# EEPROM_Temp.net
KiCad netlist of a schematic drawn in Altium Designer
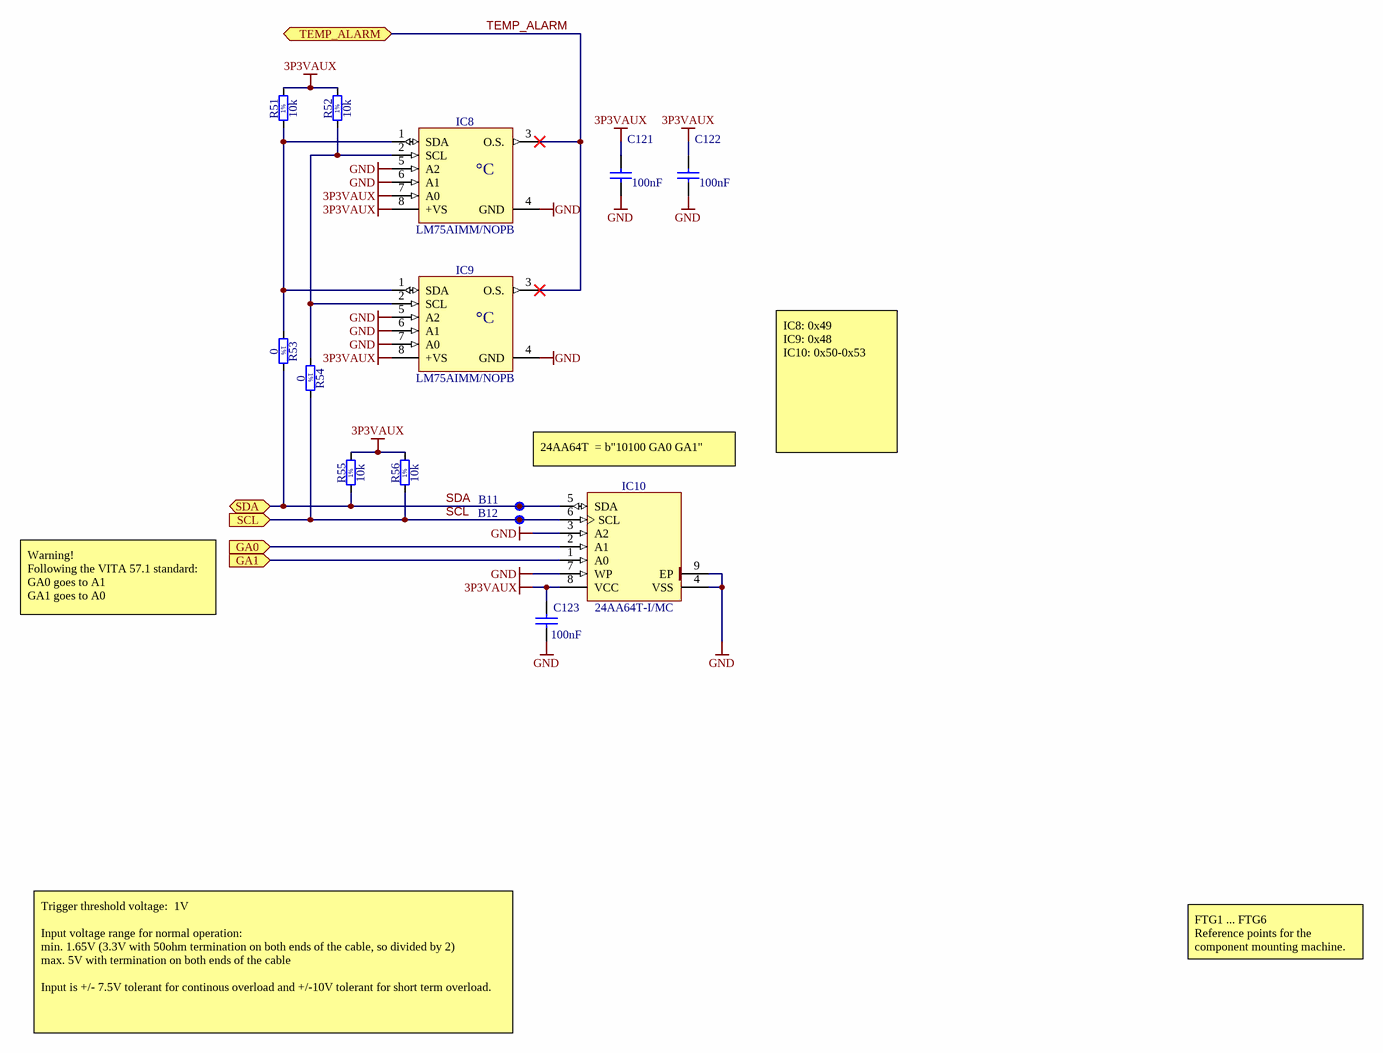
[diagram p0: EEPROM_Temp.SchDoc]

(export (version "E")
  (design (tool "Eeschema 10.0.6"))
  (components
    (comp (ref "B11")
      (value "SMD Pad")
      (footprint "C100")
      (description "Through Hole Pad")
      (fields (field (name "PART NUMBER") "SMD_PAD_D1MM") (field (name "AUTHOR") "CERN DEM JLC"))
      (libsource (lib "Eletro-mechanical") (part "Single SMD Pad (Round)"))
    )
    (comp (ref "B12")
      (value "SMD Pad")
      (footprint "C100")
      (description "Through Hole Pad")
      (fields (field (name "PART NUMBER") "SMD_PAD_D1MM") (field (name "AUTHOR") "CERN DEM JLC"))
      (libsource (lib "Eletro-mechanical") (part "Single SMD Pad (Round)"))
    )
    (comp (ref "C121")
      (value "100nF")
      (footprint "CAPC1005X55N")
      (description "Non-polarised capacitor")
      (fields
        (field (name "PART NUMBER") "CC0402_100NF_16V_10%_X5R")
        (field (name "VOLTAGE") "16V")
        (field (name "AUTHOR") "CERN DEM JLC")
      )
      (libsource (lib "Capacitors") (part "Capacitor - non polarized"))
    )
    (comp (ref "C122")
      (value "100nF")
      (footprint "CAPC1005X55N")
      (description "Non-polarised capacitor")
      (fields
        (field (name "PART NUMBER") "CC0402_100NF_16V_10%_X5R")
        (field (name "VOLTAGE") "16V")
        (field (name "AUTHOR") "CERN DEM JLC")
      )
      (libsource (lib "Capacitors") (part "Capacitor - non polarized"))
    )
    (comp (ref "C123")
      (value "100nF")
      (footprint "CAPC1005X55N")
      (description "Non-polarised capacitor")
      (fields
        (field (name "PART NUMBER") "CC0402_100NF_16V_10%_X5R")
        (field (name "VOLTAGE") "16V")
        (field (name "AUTHOR") "CERN DEM JLC")
      )
      (libsource (lib "Capacitors") (part "Capacitor - non polarized"))
    )
    (comp (ref "IC8")
      (value "LM75AIMM/NOPB")
      (footprint "SOP65P490X109-8N")
      (description "Digital Temperature Sensor and Thermal Watchdog with Two-Wire Interface")
      (fields (field (name "MANUFACTURER") "TEXAS INSTRUMENTS") (field (name "AUTHOR") "CERN DEM JLC"))
      (libsource (lib "ICs And Semiconductors") (part "LM75"))
    )
    (comp (ref "IC9")
      (value "LM75AIMM/NOPB")
      (footprint "SOP65P490X109-8N")
      (description "Digital Temperature Sensor and Thermal Watchdog with Two-Wire Interface")
      (fields (field (name "MANUFACTURER") "TEXAS INSTRUMENTS") (field (name "AUTHOR") "CERN DEM JLC"))
      (libsource (lib "ICs And Semiconductors") (part "LM75"))
    )
    (comp (ref "IC10")
      (value "24AA64T-I/MC")
      (footprint "SON50P300X200X100-9N-R175X155")
      (description "1.7V-5.5V 64K I2C Serial EEPROM")
      (fields (field (name "MANUFACTURER") "MICROCHIP TECHNOLOGY") (field (name "AUTHOR") "CERN DEM JLC"))
      (libsource (lib "ICs And Semiconductors") (part "24AA64T-I/MC"))
    )
    (comp (ref "R51")
      (value "10k")
      (footprint "RESC1005X40N")
      (description "Resistor - 1%")
      (fields
        (field (name "PART NUMBER") "R0402_10K_1%_0.0625W_100PPM")
        (field (name "POWER") "0.0625W")
        (field (name "AUTHOR") "CERN DEM JLC")
      )
      (libsource (lib "Resistors") (part "Resistor - 1%"))
    )
    (comp (ref "R52")
      (value "10k")
      (footprint "RESC1005X40N")
      (description "Resistor - 1%")
      (fields
        (field (name "PART NUMBER") "R0402_10K_1%_0.0625W_100PPM")
        (field (name "POWER") "0.0625W")
        (field (name "AUTHOR") "CERN DEM JLC")
      )
      (libsource (lib "Resistors") (part "Resistor - 1%"))
    )
    (comp (ref "R53")
      (value "0")
      (footprint "RESC1005X40N")
      (description "Resistor - 1%")
      (fields
        (field (name "PART NUMBER") "R0402_0R_JUMPER")
        (field (name "MANUFACTURER") "GENERIC")
        (field (name "AUTHOR") "CERN DEM JLC")
      )
      (libsource (lib "Resistors") (part "Resistor - 1%"))
    )
    (comp (ref "R54")
      (value "0")
      (footprint "RESC1005X40N")
      (description "Resistor - 1%")
      (fields
        (field (name "PART NUMBER") "R0402_0R_JUMPER")
        (field (name "MANUFACTURER") "GENERIC")
        (field (name "AUTHOR") "CERN DEM JLC")
      )
      (libsource (lib "Resistors") (part "Resistor - 1%"))
    )
    (comp (ref "R55")
      (value "10k")
      (footprint "RESC1005X40N")
      (description "Resistor - 1%")
      (fields
        (field (name "PART NUMBER") "R0402_10K_1%_0.0625W_100PPM")
        (field (name "POWER") "0.0625W")
        (field (name "AUTHOR") "CERN DEM JLC")
      )
      (libsource (lib "Resistors") (part "Resistor - 1%"))
    )
    (comp (ref "R56")
      (value "10k")
      (footprint "RESC1005X40N")
      (description "Resistor - 1%")
      (fields
        (field (name "PART NUMBER") "R0402_10K_1%_0.0625W_100PPM")
        (field (name "POWER") "0.0625W")
        (field (name "AUTHOR") "CERN DEM JLC")
      )
      (libsource (lib "Resistors") (part "Resistor - 1%"))
    )
  )
  (nets
    (net (code "1") (name "/GA0") (class "Default")
      (node (ref "IC10") (pin "2") (pinfunction "A1_2") (pintype "input"))
    )
    (net (code "2") (name "/GA1") (class "Default")
      (node (ref "IC10") (pin "1") (pinfunction "A0_1") (pintype "input"))
    )
    (net (code "3") (name "/SCL") (class "Default")
      (node (ref "B12") (pin "1") (pinfunction "1_1") (pintype "bidirectional"))
      (node (ref "IC10") (pin "6") (pinfunction "SCL_6") (pintype "input"))
      (node (ref "R54") (pin "2") (pinfunction "2_2") (pintype "passive"))
      (node (ref "R56") (pin "1") (pinfunction "1_1") (pintype "passive"))
    )
    (net (code "4") (name "/SDA") (class "Default")
      (node (ref "B11") (pin "1") (pinfunction "1_1") (pintype "bidirectional"))
      (node (ref "IC10") (pin "5") (pinfunction "SDA_5") (pintype "bidirectional"))
      (node (ref "R53") (pin "2") (pinfunction "2_2") (pintype "passive"))
      (node (ref "R55") (pin "1") (pinfunction "1_1") (pintype "passive"))
    )
    (net (code "5") (name "/TEMP_ALARM") (class "Default")
      (node (ref "IC8") (pin "3") (pinfunction "O.S._3") (pintype "output"))
      (node (ref "IC9") (pin "3") (pinfunction "O.S._3") (pintype "output"))
    )
    (net (code "6") (name "3P3VAUX") (class "Default")
      (node (ref "C121") (pin "1") (pinfunction "1_1") (pintype "passive"))
      (node (ref "C122") (pin "1") (pinfunction "1_1") (pintype "passive"))
      (node (ref "C123") (pin "1") (pinfunction "1_1") (pintype "passive"))
      (node (ref "IC10") (pin "8") (pinfunction "VCC_8") (pintype "power_in"))
      (node (ref "IC8") (pin "7") (pinfunction "A0_7") (pintype "input"))
      (node (ref "IC8") (pin "8") (pinfunction "+VS_8") (pintype "power_in"))
      (node (ref "IC9") (pin "8") (pinfunction "+VS_8") (pintype "power_in"))
      (node (ref "R51") (pin "2") (pinfunction "2_2") (pintype "passive"))
      (node (ref "R52") (pin "2") (pinfunction "2_2") (pintype "passive"))
      (node (ref "R55") (pin "2") (pinfunction "2_2") (pintype "passive"))
      (node (ref "R56") (pin "2") (pinfunction "2_2") (pintype "passive"))
    )
    (net (code "7") (name "GND") (class "Default")
      (node (ref "C121") (pin "2") (pinfunction "2_2") (pintype "passive"))
      (node (ref "C122") (pin "2") (pinfunction "2_2") (pintype "passive"))
      (node (ref "C123") (pin "2") (pinfunction "2_2") (pintype "passive"))
      (node (ref "IC10") (pin "3") (pinfunction "A2_3") (pintype "input"))
      (node (ref "IC10") (pin "4") (pinfunction "VSS_4") (pintype "power_in"))
      (node (ref "IC10") (pin "7") (pinfunction "WP_7") (pintype "input"))
      (node (ref "IC10") (pin "9") (pinfunction "EP_9") (pintype "power_in"))
      (node (ref "IC8") (pin "4") (pinfunction "GND_4") (pintype "power_in"))
      (node (ref "IC8") (pin "5") (pinfunction "A2_5") (pintype "input"))
      (node (ref "IC8") (pin "6") (pinfunction "A1_6") (pintype "input"))
      (node (ref "IC9") (pin "4") (pinfunction "GND_4") (pintype "power_in"))
      (node (ref "IC9") (pin "5") (pinfunction "A2_5") (pintype "input"))
      (node (ref "IC9") (pin "6") (pinfunction "A1_6") (pintype "input"))
      (node (ref "IC9") (pin "7") (pinfunction "A0_7") (pintype "input"))
    )
    (net (code "8") (name "Net-(IC8-SCL)") (class "Default")
      (node (ref "IC8") (pin "2") (pinfunction "SCL_2") (pintype "input"))
      (node (ref "IC9") (pin "2") (pinfunction "SCL_2") (pintype "input"))
      (node (ref "R52") (pin "1") (pinfunction "1_1") (pintype "passive"))
      (node (ref "R54") (pin "1") (pinfunction "1_1") (pintype "passive"))
    )
    (net (code "9") (name "Net-(IC8-SDA)") (class "Default")
      (node (ref "IC8") (pin "1") (pinfunction "SDA_1") (pintype "bidirectional"))
      (node (ref "IC9") (pin "1") (pinfunction "SDA_1") (pintype "bidirectional"))
      (node (ref "R51") (pin "1") (pinfunction "1_1") (pintype "passive"))
      (node (ref "R53") (pin "1") (pinfunction "1_1") (pintype "passive"))
    )
  )
)
